# STC12C5A60S2.net
KiCad netlist of a schematic drawn in Altium Designer
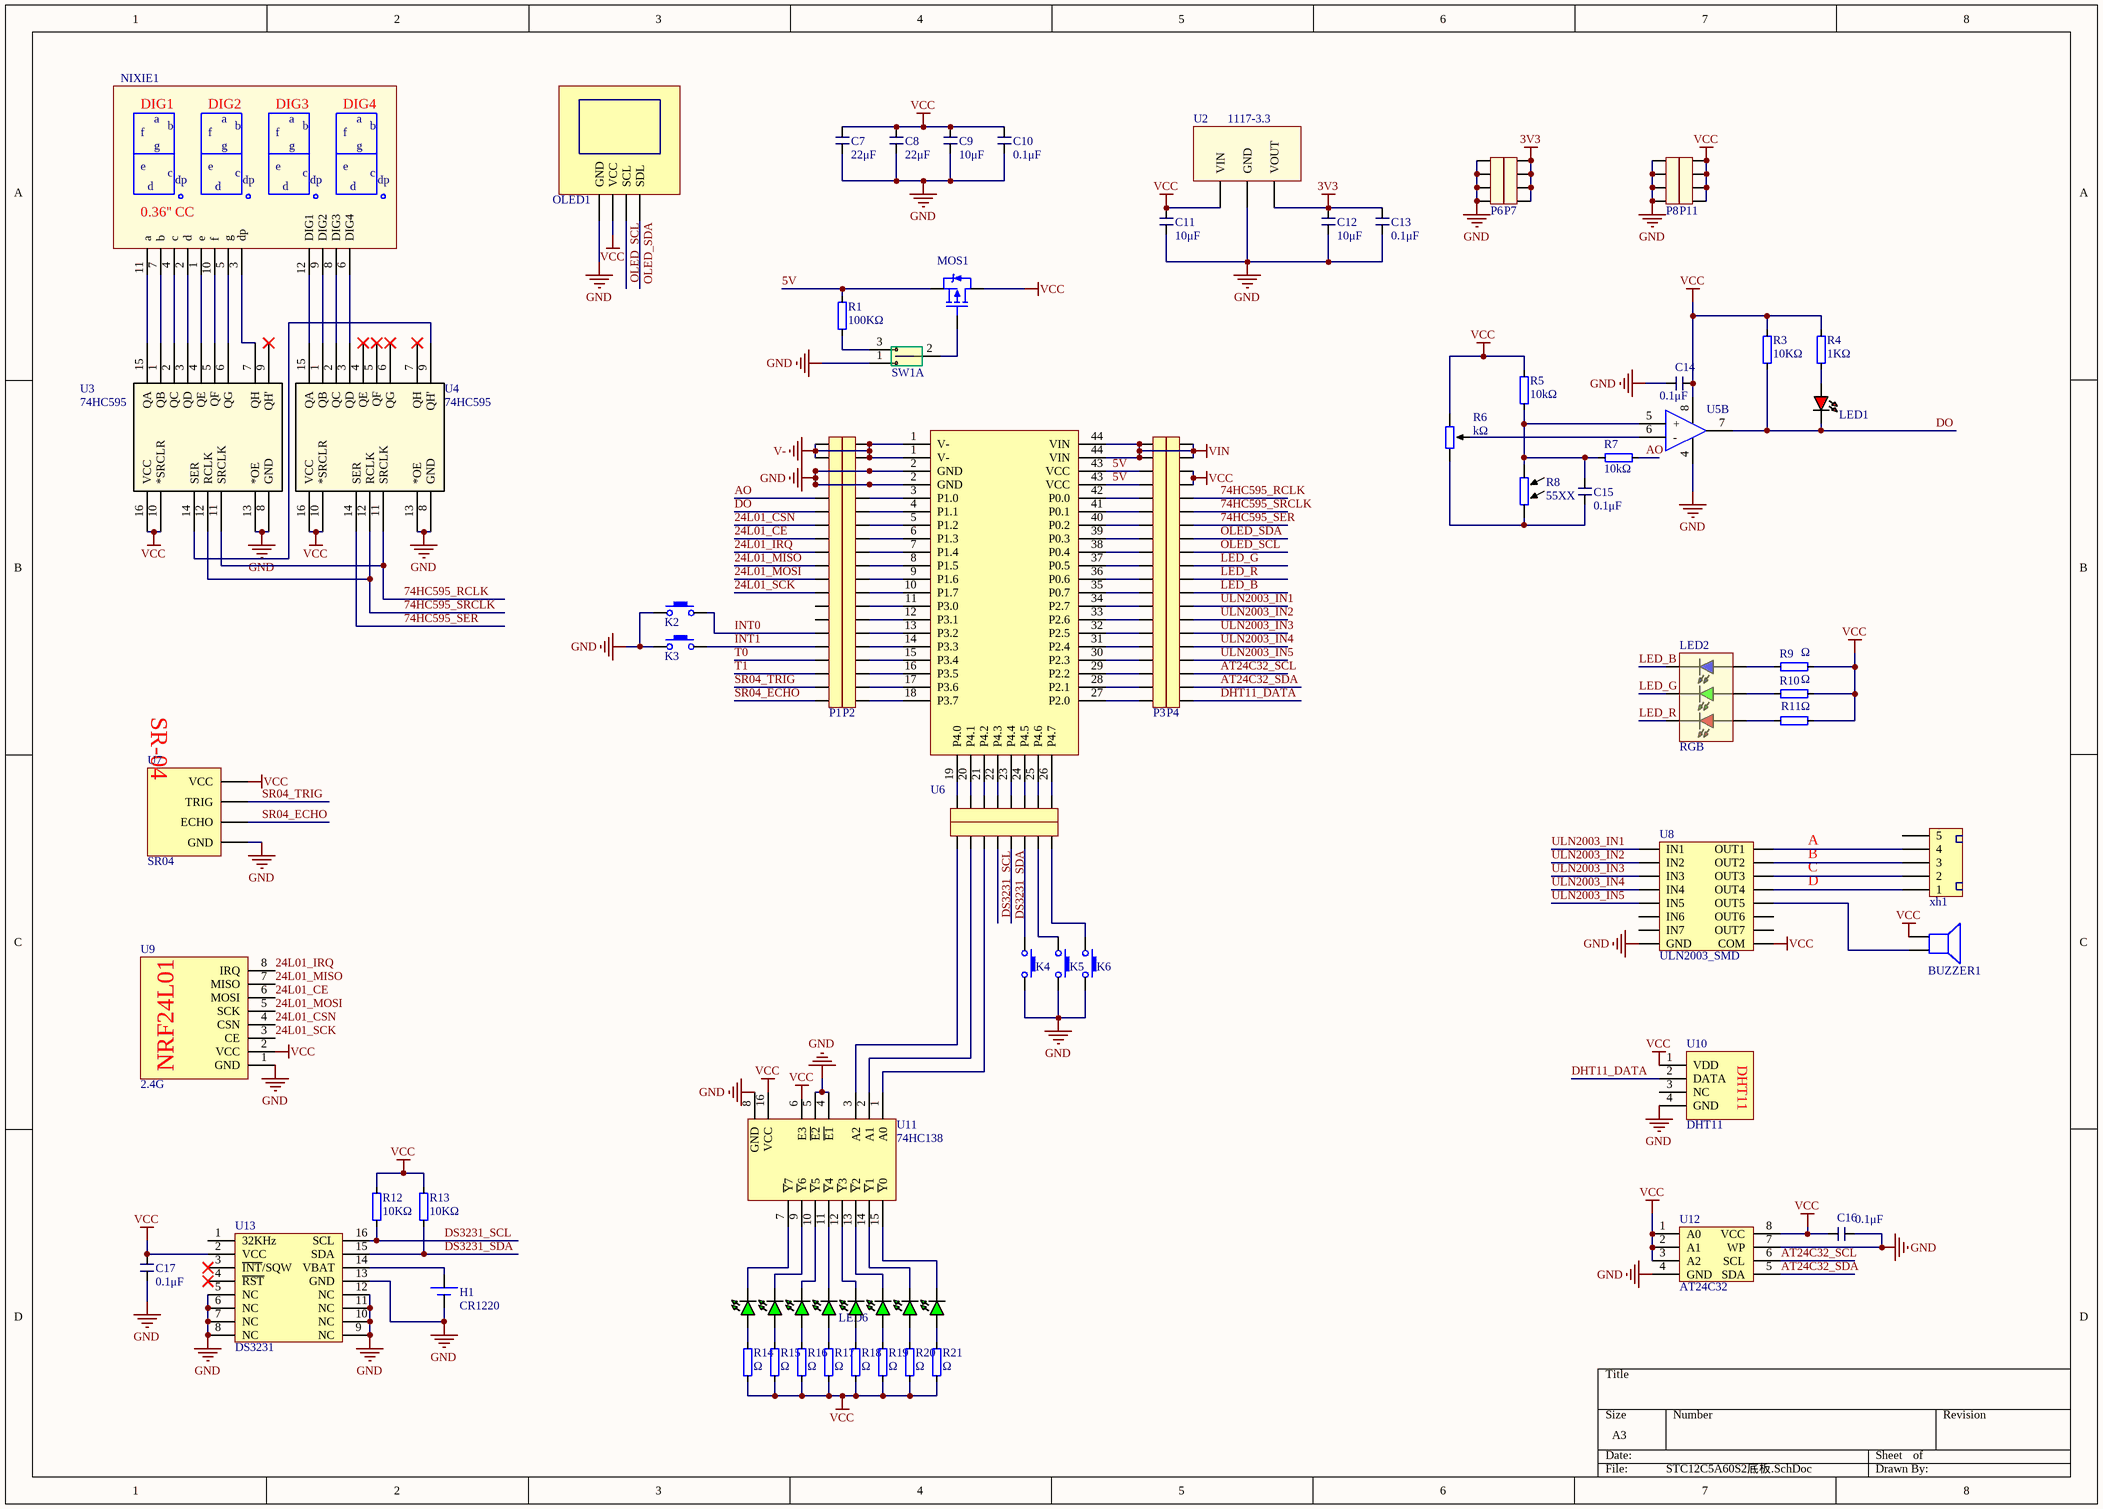
[diagram p0: STC12C5A60S2底板.SchDoc]

(export (version "E")
  (design (tool "Eeschema 10.0.6"))
  (components
    (comp (ref "BUZZER1")
      (value "BUZZER 9.6X5.5_4MM")
      (footprint "BUZZER9.6x4_4mm")
      (libsource (lib "节能库") (part "BUZZER 9.6X5.5_4MM"))
    )
    (comp (ref "C7") (value "22μF") (footprint "C_0805") (libsource (lib "节能库") (part "C_0805")))
    (comp (ref "C8") (value "22μF") (footprint "C_0805") (libsource (lib "节能库") (part "C_0805")))
    (comp (ref "C9") (value "10μF") (footprint "C_0805") (libsource (lib "节能库") (part "C_0805")))
    (comp (ref "C10") (value "0.1μF") (footprint "C_0805") (libsource (lib "节能库") (part "C_0805")))
    (comp (ref "C11") (value "10μF") (footprint "C_0805") (libsource (lib "节能库") (part "C_0805")))
    (comp (ref "C12") (value "10μF") (footprint "C_0805") (libsource (lib "节能库") (part "C_0805")))
    (comp (ref "C13") (value "0.1μF") (footprint "C_0805") (libsource (lib "节能库") (part "C_0805")))
    (comp (ref "C14") (value "0.1μF") (footprint "C_0805") (libsource (lib "节能库") (part "C_0805")))
    (comp (ref "C15") (value "0.1μF") (footprint "C_0805") (libsource (lib "节能库") (part "C_0805")))
    (comp (ref "C16") (value "0.1μF") (footprint "C_0805") (libsource (lib "节能库") (part "C_0805")))
    (comp (ref "C17") (value "0.1μF") (footprint "C_0805") (libsource (lib "节能库") (part "C_0805")))
    (comp (ref "H1")
      (value "CR1220")
      (footprint "holder_CR1220_SMD")
      (libsource (lib "节能库") (part "holder_CR1220_SMD"))
    )
    (comp (ref "K2")
      (value "TACT SWITCH_4_DIP")
      (footprint "TACT SWITCH_4_DIP")
      (libsource (lib "") (part "TACT SWITCH_4_DIP_1"))
    )
    (comp (ref "K3")
      (value "TACT SWITCH_4_DIP")
      (footprint "TACT SWITCH_4_DIP")
      (libsource (lib "") (part "TACT SWITCH_4_DIP_1"))
    )
    (comp (ref "K4")
      (value "TACT SWITCH_4_DIP")
      (footprint "TACT SWITCH_4_DIP")
      (libsource (lib "节能库") (part "TACT SWITCH_4_DIP"))
    )
    (comp (ref "K5")
      (value "TACT SWITCH_4_DIP")
      (footprint "TACT SWITCH_4_DIP")
      (libsource (lib "节能库") (part "TACT SWITCH_4_DIP"))
    )
    (comp (ref "K6")
      (value "TACT SWITCH_4_DIP")
      (footprint "TACT SWITCH_4_DIP")
      (libsource (lib "节能库") (part "TACT SWITCH_4_DIP"))
    )
    (comp (ref "LED1")
      (value "LED_0603-R")
      (footprint "LED_0603-R")
      (libsource (lib "节能库") (part "LED_0603-R"))
    )
    (comp (ref "LED2") (value "RGB") (footprint "LED 5050_RGB") (libsource (lib "节能库") (part "LED_5050_RGB")))
    (comp (ref "LED3")
      (value "LED_0603-G")
      (footprint "LED_0603-G")
      (libsource (lib "节能库") (part "LED_0603-G"))
    )
    (comp (ref "LED4")
      (value "LED_0603-G")
      (footprint "LED_0603-G")
      (libsource (lib "节能库") (part "LED_0603-G"))
    )
    (comp (ref "LED5")
      (value "LED_0603-G")
      (footprint "LED_0603-G")
      (libsource (lib "节能库") (part "LED_0603-G"))
    )
    (comp (ref "LED6")
      (value "LED_0603-G")
      (footprint "LED_0603-G")
      (libsource (lib "节能库") (part "LED_0603-G"))
    )
    (comp (ref "LED7")
      (value "LED_0603-G")
      (footprint "LED_0603-G")
      (libsource (lib "节能库") (part "LED_0603-G"))
    )
    (comp (ref "LED8")
      (value "LED_0603-G")
      (footprint "LED_0603-G")
      (libsource (lib "节能库") (part "LED_0603-G"))
    )
    (comp (ref "LED9")
      (value "LED_0603-G")
      (footprint "LED_0603-G")
      (libsource (lib "节能库") (part "LED_0603-G"))
    )
    (comp (ref "LED10")
      (value "LED_0603-G")
      (footprint "LED_0603-G")
      (libsource (lib "节能库") (part "LED_0603-G"))
    )
    (comp (ref "MOS1") (value "SI2301") (footprint "SOT_23_3") (libsource (lib "节能库") (part "SI2301")))
    (comp (ref "NIXIE1")
      (value "Nixie Tube_CC(0.36in)_4")
      (footprint "Nixie Tube_4(0.36in)")
      (libsource (lib "节能库") (part "Nixie Tube_CC(0.36in)_4"))
    )
    (comp (ref "OLED1")
      (value "0.96''")
      (footprint "OLED 0.96''")
      (libsource (lib "节能库") (part "OLED 0.96''_module"))
    )
    (comp (ref "P1") (value "PIN20") (footprint "PIN_20") (libsource (lib "") (part "PIN20_1")))
    (comp (ref "P2") (value "PIN20") (footprint "PIN_20") (libsource (lib "节能库") (part "PIN20")))
    (comp (ref "P3") (value "PIN20") (footprint "PIN_20") (libsource (lib "") (part "PIN20_1")))
    (comp (ref "P4") (value "PIN20") (footprint "PIN_20") (libsource (lib "节能库") (part "PIN20")))
    (comp (ref "P6") (value "PIN4") (footprint "PIN_4") (libsource (lib "") (part "PIN4_1")))
    (comp (ref "P7") (value "PIN4") (footprint "PIN_4") (libsource (lib "节能库") (part "PIN4")))
    (comp (ref "P8") (value "PIN4") (footprint "PIN_4") (libsource (lib "") (part "PIN4_1")))
    (comp (ref "P11") (value "PIN4") (footprint "PIN_4") (libsource (lib "节能库") (part "PIN4")))
    (comp (ref "P12") (value "PIN8") (footprint "PIN_8") (libsource (lib "") (part "PIN8_1")))
    (comp (ref "P13") (value "PIN8") (footprint "PIN_8") (libsource (lib "节能库") (part "PIN8")))
    (comp (ref "R1") (value "100KΩ") (footprint "R_0805") (libsource (lib "节能库") (part "R_0805")))
    (comp (ref "R3") (value "10KΩ") (footprint "R_0805") (libsource (lib "节能库") (part "R_0805")))
    (comp (ref "R4") (value "1KΩ") (footprint "R_0805") (libsource (lib "节能库") (part "R_0805")))
    (comp (ref "R5") (value "10kΩ") (footprint "R_0805") (libsource (lib "节能库") (part "R_0805")))
    (comp (ref "R6") (value "kΩ") (footprint "RP_3362P") (libsource (lib "节能库") (part "RP_3362P")))
    (comp (ref "R7") (value "10kΩ") (footprint "R_0805") (libsource (lib "节能库") (part "R_0805")))
    (comp (ref "R8") (value "55XX") (footprint "GM55-55XX") (libsource (lib "节能库") (part "GM55-55XX")))
    (comp (ref "R9") (value "Ω") (footprint "R_0805") (libsource (lib "节能库") (part "R_0805")))
    (comp (ref "R10") (value "Ω") (footprint "R_0805") (libsource (lib "节能库") (part "R_0805")))
    (comp (ref "R11") (value "Ω") (footprint "R_0805") (libsource (lib "节能库") (part "R_0805")))
    (comp (ref "R12") (value "10KΩ") (footprint "R_0805") (libsource (lib "节能库") (part "R_0805")))
    (comp (ref "R13") (value "10KΩ") (footprint "R_0805") (libsource (lib "节能库") (part "R_0805")))
    (comp (ref "R14") (value "Ω") (footprint "R_0805") (libsource (lib "节能库") (part "R_0805")))
    (comp (ref "R15") (value "Ω") (footprint "R_0805") (libsource (lib "节能库") (part "R_0805")))
    (comp (ref "R16") (value "Ω") (footprint "R_0805") (libsource (lib "节能库") (part "R_0805")))
    (comp (ref "R17") (value "Ω") (footprint "R_0805") (libsource (lib "节能库") (part "R_0805")))
    (comp (ref "R18") (value "Ω") (footprint "R_0805") (libsource (lib "节能库") (part "R_0805")))
    (comp (ref "R19") (value "Ω") (footprint "R_0805") (libsource (lib "节能库") (part "R_0805")))
    (comp (ref "R20") (value "Ω") (footprint "R_0805") (libsource (lib "节能库") (part "R_0805")))
    (comp (ref "R21") (value "Ω") (footprint "R_0805") (libsource (lib "节能库") (part "R_0805")))
    (comp (ref "SW1")
      (value "switchi_slide(SMD)")
      (footprint "switchi_slide(SMD)")
      (libsource (lib "节能库") (part "switchi_slide(SMD)"))
    )
    (comp (ref "U2") (value "1117-3.3") (footprint "SOT_223") (libsource (lib "节能库") (part "AMS1117-3.3")))
    (comp (ref "U3") (value "74HC595") (footprint "SOP_16") (libsource (lib "节能库") (part "74HC595")))
    (comp (ref "U4") (value "74HC595") (footprint "SOP_16") (libsource (lib "节能库") (part "74HC595")))
    (comp (ref "U5") (value "LM393_DIP") (footprint "SOP_8") (libsource (lib "节能库") (part "LM393_DIP")))
    (comp (ref "U6")
      (value "socket")
      (footprint "STC12_moudle")
      (libsource (lib "节能库") (part "STC12C_module"))
    )
    (comp (ref "U7") (value "SR04") (footprint "SR04") (libsource (lib "节能库") (part "SR04")))
    (comp (ref "U8") (value "ULN2003_SMD") (footprint "SOP_16") (libsource (lib "节能库") (part "ULN2003_SMD")))
    (comp (ref "U9") (value "2.4G") (footprint "NRF24L01") (libsource (lib "节能库") (part "NRF24L01")))
    (comp (ref "U10") (value "DHT11") (footprint "DHT11") (libsource (lib "节能库") (part "DHT11")))
    (comp (ref "U11") (value "74HC138") (footprint "SOP_16") (libsource (lib "节能库") (part "74HC138")))
    (comp (ref "U12") (value "AT24C32") (footprint "SOP_8") (libsource (lib "节能库") (part "AT24C32")))
    (comp (ref "U13") (value "DS3231") (footprint "SOP_16") (libsource (lib "节能库") (part "DS3231_SOP16")))
    (comp (ref "xh1") (value "XH2.54_5") (footprint "XH2.54_5") (libsource (lib "节能库") (part "XH2.54_5")))
  )
  (nets
    (net (code "1") (name "/5V") (class "Default")
      (node (ref "MOS1") (pin "2") (pinfunction "S_2") (pintype "passive"))
      (node (ref "P3") (pin "17") (pinfunction "17_17") (pintype "passive"))
      (node (ref "P3") (pin "18") (pinfunction "18_18") (pintype "passive"))
      (node (ref "R1") (pin "2") (pintype "passive"))
      (node (ref "U6") (pin "43") (pinfunction "VCC_43") (pintype "passive"))
    )
    (net (code "2") (name "/24L01_CE") (class "Default")
      (node (ref "P1") (pin "13") (pinfunction "13_13") (pintype "passive"))
      (node (ref "U9") (pin "6") (pinfunction "MOSI_6") (pintype "passive"))
    )
    (net (code "3") (name "/24L01_CSN") (class "Default")
      (node (ref "P1") (pin "14") (pinfunction "14_14") (pintype "passive"))
      (node (ref "U9") (pin "4") (pinfunction "CSN_4") (pintype "passive"))
    )
    (net (code "4") (name "/24L01_IRQ") (class "Default")
      (node (ref "P1") (pin "12") (pinfunction "12_12") (pintype "passive"))
      (node (ref "U9") (pin "8") (pinfunction "IRQ_8") (pintype "passive"))
    )
    (net (code "5") (name "/24L01_MISO") (class "Default")
      (node (ref "P1") (pin "11") (pinfunction "11_11") (pintype "passive"))
      (node (ref "U9") (pin "7") (pinfunction "MISO_7") (pintype "passive"))
    )
    (net (code "6") (name "/24L01_MOSI") (class "Default")
      (node (ref "P1") (pin "10") (pinfunction "10_10") (pintype "passive"))
      (node (ref "U9") (pin "5") (pinfunction "SCK_5") (pintype "passive"))
    )
    (net (code "7") (name "/24L01_SCK") (class "Default")
      (node (ref "P1") (pin "9") (pinfunction "9_9") (pintype "passive"))
      (node (ref "U9") (pin "3") (pinfunction "CE_3") (pintype "passive"))
    )
    (net (code "8") (name "/74HC595_RCLK") (class "Default")
      (node (ref "P4") (pin "16") (pinfunction "16_16") (pintype "passive"))
      (node (ref "U3") (pin "11") (pinfunction "SRCLK_11") (pintype "passive"))
      (node (ref "U4") (pin "11") (pinfunction "SRCLK_11") (pintype "passive"))
    )
    (net (code "9") (name "/74HC595_SER") (class "Default")
      (node (ref "P4") (pin "14") (pinfunction "14_14") (pintype "passive"))
      (node (ref "U4") (pin "14") (pinfunction "SER_14") (pintype "passive"))
    )
    (net (code "10") (name "/74HC595_SRCLK") (class "Default")
      (node (ref "P4") (pin "15") (pinfunction "15_15") (pintype "passive"))
      (node (ref "U3") (pin "12") (pinfunction "RCLK_12") (pintype "passive"))
      (node (ref "U4") (pin "12") (pinfunction "RCLK_12") (pintype "passive"))
    )
    (net (code "11") (name "/AO") (class "Default")
      (node (ref "P1") (pin "16") (pinfunction "16_16") (pintype "passive"))
      (node (ref "R7") (pin "2") (pintype "passive"))
    )
    (net (code "12") (name "/AT24C32_SCL") (class "Default")
      (node (ref "P4") (pin "3") (pinfunction "3_3") (pintype "passive"))
      (node (ref "U12") (pin "6") (pinfunction "SCL_6") (pintype "passive"))
    )
    (net (code "13") (name "/AT24C32_SDA") (class "Default")
      (node (ref "P4") (pin "2") (pinfunction "2_2") (pintype "passive"))
      (node (ref "U12") (pin "5") (pinfunction "SDA_5") (pintype "passive"))
    )
    (net (code "14") (name "/DHT11_DATA") (class "Default")
      (node (ref "P4") (pin "1") (pinfunction "1_1") (pintype "passive"))
      (node (ref "U10") (pin "2") (pinfunction "DATA_2") (pintype "passive"))
    )
    (net (code "15") (name "/DO") (class "Default")
      (node (ref "LED1") (pin "2") (pinfunction "2_2") (pintype "passive"))
      (node (ref "P1") (pin "15") (pinfunction "15_15") (pintype "passive"))
      (node (ref "R3") (pin "1") (pintype "passive"))
      (node (ref "U5") (pin "7") (pintype "passive"))
    )
    (net (code "16") (name "/DS3231_SCL") (class "Default")
      (node (ref "P13") (pin "4") (pinfunction "4_4") (pintype "passive"))
      (node (ref "R12") (pin "1") (pintype "passive"))
      (node (ref "U13") (pin "16") (pinfunction "SCL_16") (pintype "passive"))
    )
    (net (code "17") (name "/DS3231_SDA") (class "Default")
      (node (ref "P13") (pin "5") (pinfunction "5_5") (pintype "passive"))
      (node (ref "R13") (pin "1") (pintype "passive"))
      (node (ref "U13") (pin "15") (pinfunction "SDA_15") (pintype "passive"))
    )
    (net (code "18") (name "/INT0") (class "Default")
      (node (ref "K2") (pin "2") (pinfunction "2_2") (pintype "passive"))
      (node (ref "P1") (pin "6") (pinfunction "6_6") (pintype "passive"))
    )
    (net (code "19") (name "/INT1") (class "Default")
      (node (ref "K3") (pin "2") (pinfunction "2_2") (pintype "passive"))
      (node (ref "P1") (pin "5") (pinfunction "5_5") (pintype "passive"))
    )
    (net (code "20") (name "/LED_B") (class "Default")
      (node (ref "LED2") (pin "1") (pinfunction "1_1") (pintype "passive"))
      (node (ref "P4") (pin "9") (pinfunction "9_9") (pintype "passive"))
    )
    (net (code "21") (name "/LED_G") (class "Default")
      (node (ref "LED2") (pin "5") (pinfunction "5_5") (pintype "passive"))
      (node (ref "P4") (pin "11") (pinfunction "11_11") (pintype "passive"))
    )
    (net (code "22") (name "/LED_R") (class "Default")
      (node (ref "LED2") (pin "3") (pinfunction "3_3") (pintype "passive"))
      (node (ref "P4") (pin "10") (pinfunction "10_10") (pintype "passive"))
    )
    (net (code "23") (name "/OLED_SCL") (class "Default")
      (node (ref "OLED1") (pin "3") (pinfunction "SCL_3") (pintype "passive"))
      (node (ref "P4") (pin "12") (pinfunction "12_12") (pintype "passive"))
    )
    (net (code "24") (name "/OLED_SDA") (class "Default")
      (node (ref "OLED1") (pin "4") (pinfunction "SDL_4") (pintype "passive"))
      (node (ref "P4") (pin "13") (pinfunction "13_13") (pintype "passive"))
    )
    (net (code "25") (name "/SR04_ECHO") (class "Default")
      (node (ref "P1") (pin "1") (pinfunction "1_1") (pintype "passive"))
      (node (ref "U7") (pin "3") (pinfunction "ECHO_3") (pintype "passive"))
    )
    (net (code "26") (name "/SR04_TRIG") (class "Default")
      (node (ref "P1") (pin "2") (pinfunction "2_2") (pintype "passive"))
      (node (ref "U7") (pin "2") (pinfunction "TRIG_2") (pintype "passive"))
    )
    (net (code "27") (name "/T0") (class "Default")
      (node (ref "P1") (pin "4") (pinfunction "4_4") (pintype "passive"))
    )
    (net (code "28") (name "/T1") (class "Default")
      (node (ref "P1") (pin "3") (pinfunction "3_3") (pintype "passive"))
    )
    (net (code "29") (name "/ULN2003_IN1") (class "Default")
      (node (ref "P4") (pin "8") (pinfunction "8_8") (pintype "passive"))
      (node (ref "U8") (pin "1") (pinfunction "IN1_1") (pintype "passive"))
    )
    (net (code "30") (name "/ULN2003_IN2") (class "Default")
      (node (ref "P4") (pin "7") (pinfunction "7_7") (pintype "passive"))
      (node (ref "U8") (pin "2") (pinfunction "IN2_2") (pintype "passive"))
    )
    (net (code "31") (name "/ULN2003_IN3") (class "Default")
      (node (ref "P4") (pin "6") (pinfunction "6_6") (pintype "passive"))
      (node (ref "U8") (pin "3") (pinfunction "IN3_3") (pintype "passive"))
    )
    (net (code "32") (name "/ULN2003_IN4") (class "Default")
      (node (ref "P4") (pin "5") (pinfunction "5_5") (pintype "passive"))
      (node (ref "U8") (pin "4") (pinfunction "IN4_4") (pintype "passive"))
    )
    (net (code "33") (name "/ULN2003_IN5") (class "Default")
      (node (ref "P4") (pin "4") (pinfunction "4_4") (pintype "passive"))
      (node (ref "U8") (pin "5") (pinfunction "IN5_5") (pintype "passive"))
    )
    (net (code "34") (name "3V3") (class "Default")
      (node (ref "C12") (pin "1") (pinfunction "1_1") (pintype "passive"))
      (node (ref "C13") (pin "1") (pinfunction "1_1") (pintype "passive"))
      (node (ref "P7") (pin "1") (pinfunction "1_1") (pintype "passive"))
      (node (ref "P7") (pin "2") (pinfunction "2_2") (pintype "passive"))
      (node (ref "P7") (pin "3") (pinfunction "3_3") (pintype "passive"))
      (node (ref "P7") (pin "4") (pinfunction "4_4") (pintype "passive"))
      (node (ref "U2") (pin "2") (pinfunction "VOUT_2") (pintype "passive"))
    )
    (net (code "35") (name "GND") (class "Default")
      (node (ref "C10") (pin "2") (pinfunction "2_2") (pintype "passive"))
      (node (ref "C11") (pin "2") (pinfunction "2_2") (pintype "passive"))
      (node (ref "C12") (pin "2") (pinfunction "2_2") (pintype "passive"))
      (node (ref "C13") (pin "2") (pinfunction "2_2") (pintype "passive"))
      (node (ref "C14") (pin "1") (pinfunction "1_1") (pintype "passive"))
      (node (ref "C16") (pin "2") (pinfunction "2_2") (pintype "passive"))
      (node (ref "C17") (pin "2") (pinfunction "2_2") (pintype "passive"))
      (node (ref "C7") (pin "2") (pinfunction "2_2") (pintype "passive"))
      (node (ref "C8") (pin "2") (pinfunction "2_2") (pintype "passive"))
      (node (ref "C9") (pin "2") (pinfunction "2_2") (pintype "passive"))
      (node (ref "H1") (pin "2") (pinfunction "-_2") (pintype "passive"))
      (node (ref "K2") (pin "1") (pinfunction "1_1") (pintype "passive"))
      (node (ref "K3") (pin "1") (pinfunction "1_1") (pintype "passive"))
      (node (ref "K4") (pin "2") (pinfunction "2_2") (pintype "passive"))
      (node (ref "K5") (pin "2") (pinfunction "2_2") (pintype "passive"))
      (node (ref "K6") (pin "2") (pinfunction "2_2") (pintype "passive"))
      (node (ref "OLED1") (pin "1") (pinfunction "GND_1") (pintype "passive"))
      (node (ref "P1") (pin "17") (pinfunction "17_17") (pintype "passive"))
      (node (ref "P1") (pin "18") (pinfunction "18_18") (pintype "passive"))
      (node (ref "P2") (pin "17") (pinfunction "17_17") (pintype "passive"))
      (node (ref "P2") (pin "18") (pinfunction "18_18") (pintype "passive"))
      (node (ref "P6") (pin "1") (pinfunction "1_1") (pintype "passive"))
      (node (ref "P6") (pin "2") (pinfunction "2_2") (pintype "passive"))
      (node (ref "P6") (pin "3") (pinfunction "3_3") (pintype "passive"))
      (node (ref "P6") (pin "4") (pinfunction "4_4") (pintype "passive"))
      (node (ref "P8") (pin "1") (pinfunction "1_1") (pintype "passive"))
      (node (ref "P8") (pin "2") (pinfunction "2_2") (pintype "passive"))
      (node (ref "P8") (pin "3") (pinfunction "3_3") (pintype "passive"))
      (node (ref "P8") (pin "4") (pinfunction "4_4") (pintype "passive"))
      (node (ref "SW1") (pin "1") (pinfunction "1_1") (pintype "passive"))
      (node (ref "U10") (pin "4") (pinfunction "GND_4") (pintype "passive"))
      (node (ref "U11") (pin "4") (pinfunction "~{E1}_4") (pintype "passive"))
      (node (ref "U11") (pin "5") (pinfunction "~{E2}_5") (pintype "passive"))
      (node (ref "U11") (pin "8") (pinfunction "GND_8") (pintype "passive"))
      (node (ref "U12") (pin "4") (pinfunction "GND_4") (pintype "passive"))
      (node (ref "U12") (pin "7") (pinfunction "WP_7") (pintype "passive"))
      (node (ref "U13") (pin "10") (pinfunction "NC_10") (pintype "passive"))
      (node (ref "U13") (pin "11") (pinfunction "NC_11") (pintype "passive"))
      (node (ref "U13") (pin "12") (pinfunction "NC_12") (pintype "passive"))
      (node (ref "U13") (pin "13") (pinfunction "GND_13") (pintype "passive"))
      (node (ref "U13") (pin "5") (pinfunction "NC_5") (pintype "passive"))
      (node (ref "U13") (pin "6") (pinfunction "NC_6") (pintype "passive"))
      (node (ref "U13") (pin "7") (pinfunction "NC_7") (pintype "passive"))
      (node (ref "U13") (pin "8") (pinfunction "NC_8") (pintype "passive"))
      (node (ref "U13") (pin "9") (pinfunction "NC_9") (pintype "passive"))
      (node (ref "U2") (pin "1") (pinfunction "GND_1") (pintype "passive"))
      (node (ref "U3") (pin "13") (pinfunction "*OE_13") (pintype "passive"))
      (node (ref "U3") (pin "8") (pinfunction "GND_8") (pintype "passive"))
      (node (ref "U4") (pin "13") (pinfunction "*OE_13") (pintype "passive"))
      (node (ref "U4") (pin "8") (pinfunction "GND_8") (pintype "passive"))
      (node (ref "U5") (pin "4") (pinfunction "GND_4") (pintype "passive"))
      (node (ref "U6") (pin "2") (pinfunction "GND_2") (pintype "passive"))
      (node (ref "U7") (pin "4") (pinfunction "GND_4") (pintype "passive"))
      (node (ref "U8") (pin "8") (pinfunction "GND_8") (pintype "passive"))
      (node (ref "U9") (pin "1") (pinfunction "GND_1") (pintype "passive"))
    )
    (net (code "36") (name "Net-(C15-Pad2)") (class "Default")
      (node (ref "C15") (pin "2") (pinfunction "2_2") (pintype "passive"))
      (node (ref "R6") (pin "3") (pinfunction "3_3") (pintype "passive"))
      (node (ref "R8") (pin "2") (pintype "passive"))
    )
    (net (code "37") (name "Net-(H1-+)") (class "Default")
      (node (ref "H1") (pin "1") (pinfunction "+_1") (pintype "passive"))
      (node (ref "U13") (pin "14") (pinfunction "VBAT_14") (pintype "passive"))
    )
    (net (code "38") (name "Net-(K4-Pad1)") (class "Default")
      (node (ref "K4") (pin "1") (pinfunction "1_1") (pintype "passive"))
      (node (ref "P13") (pin "6") (pinfunction "6_6") (pintype "passive"))
    )
    (net (code "39") (name "Net-(K5-Pad1)") (class "Default")
      (node (ref "K5") (pin "1") (pinfunction "1_1") (pintype "passive"))
      (node (ref "P13") (pin "7") (pinfunction "7_7") (pintype "passive"))
    )
    (net (code "40") (name "Net-(K6-Pad1)") (class "Default")
      (node (ref "K6") (pin "1") (pinfunction "1_1") (pintype "passive"))
      (node (ref "P13") (pin "8") (pinfunction "8_8") (pintype "passive"))
    )
    (net (code "41") (name "Net-(LED1-Pad1)") (class "Default")
      (node (ref "LED1") (pin "1") (pinfunction "1_1") (pintype "passive"))
      (node (ref "R4") (pin "1") (pintype "passive"))
    )
    (net (code "42") (name "Net-(LED2-Pad2)") (class "Default")
      (node (ref "LED2") (pin "2") (pinfunction "2_2") (pintype "passive"))
      (node (ref "R9") (pin "1") (pintype "passive"))
    )
    (net (code "43") (name "Net-(LED2-Pad4)") (class "Default")
      (node (ref "LED2") (pin "4") (pinfunction "4_4") (pintype "passive"))
      (node (ref "R11") (pin "1") (pintype "passive"))
    )
    (net (code "44") (name "Net-(LED2-Pad6)") (class "Default")
      (node (ref "LED2") (pin "6") (pinfunction "6_6") (pintype "passive"))
      (node (ref "R10") (pin "1") (pintype "passive"))
    )
    (net (code "45") (name "Net-(LED3-Pad1)") (class "Default")
      (node (ref "LED3") (pin "1") (pinfunction "1_1") (pintype "passive"))
      (node (ref "R14") (pin "2") (pintype "passive"))
    )
    (net (code "46") (name "Net-(LED4-Pad1)") (class "Default")
      (node (ref "LED4") (pin "1") (pinfunction "1_1") (pintype "passive"))
      (node (ref "R15") (pin "2") (pintype "passive"))
    )
    (net (code "47") (name "Net-(LED5-Pad1)") (class "Default")
      (node (ref "LED5") (pin "1") (pinfunction "1_1") (pintype "passive"))
      (node (ref "R16") (pin "2") (pintype "passive"))
    )
    (net (code "48") (name "Net-(LED6-Pad1)") (class "Default")
      (node (ref "LED6") (pin "1") (pinfunction "1_1") (pintype "passive"))
      (node (ref "R17") (pin "2") (pintype "passive"))
    )
    (net (code "49") (name "Net-(LED7-Pad1)") (class "Default")
      (node (ref "LED7") (pin "1") (pinfunction "1_1") (pintype "passive"))
      (node (ref "R18") (pin "2") (pintype "passive"))
    )
    (net (code "50") (name "Net-(LED8-Pad1)") (class "Default")
      (node (ref "LED8") (pin "1") (pinfunction "1_1") (pintype "passive"))
      (node (ref "R19") (pin "2") (pintype "passive"))
    )
    (net (code "51") (name "Net-(LED9-Pad1)") (class "Default")
      (node (ref "LED9") (pin "1") (pinfunction "1_1") (pintype "passive"))
      (node (ref "R20") (pin "2") (pintype "passive"))
    )
    (net (code "52") (name "Net-(LED10-Pad1)") (class "Default")
      (node (ref "LED10") (pin "1") (pinfunction "1_1") (pintype "passive"))
      (node (ref "R21") (pin "2") (pintype "passive"))
    )
    (net (code "53") (name "Net-(MOS1-G)") (class "Default")
      (node (ref "MOS1") (pin "1") (pinfunction "G_1") (pintype "passive"))
      (node (ref "SW1") (pin "2") (pinfunction "2_2") (pintype "passive"))
    )
    (net (code "54") (name "Net-(NIXIE1-DIG1)") (class "Default")
      (node (ref "NIXIE1") (pin "12") (pinfunction "DIG1_12") (pintype "passive"))
      (node (ref "U4") (pin "15") (pinfunction "QA_15") (pintype "passive"))
    )
    (net (code "55") (name "Net-(NIXIE1-DIG2)") (class "Default")
      (node (ref "NIXIE1") (pin "9") (pinfunction "DIG2_9") (pintype "passive"))
      (node (ref "U4") (pin "1") (pinfunction "QB_1") (pintype "passive"))
    )
    (net (code "56") (name "Net-(NIXIE1-DIG3)") (class "Default")
      (node (ref "NIXIE1") (pin "8") (pinfunction "DIG3_8") (pintype "passive"))
      (node (ref "U4") (pin "2") (pinfunction "QC_2") (pintype "passive"))
    )
    (net (code "57") (name "Net-(NIXIE1-DIG4)") (class "Default")
      (node (ref "NIXIE1") (pin "6") (pinfunction "DIG4_6") (pintype "passive"))
      (node (ref "U4") (pin "3") (pinfunction "QD_3") (pintype "passive"))
    )
    (net (code "58") (name "Net-(NIXIE1-a)") (class "Default")
      (node (ref "NIXIE1") (pin "11") (pinfunction "a_11") (pintype "passive"))
      (node (ref "U3") (pin "15") (pinfunction "QA_15") (pintype "passive"))
    )
    (net (code "59") (name "Net-(NIXIE1-b)") (class "Default")
      (node (ref "NIXIE1") (pin "7") (pinfunction "b_7") (pintype "passive"))
      (node (ref "U3") (pin "1") (pinfunction "QB_1") (pintype "passive"))
    )
    (net (code "60") (name "Net-(NIXIE1-c)") (class "Default")
      (node (ref "NIXIE1") (pin "4") (pinfunction "c_4") (pintype "passive"))
      (node (ref "U3") (pin "2") (pinfunction "QC_2") (pintype "passive"))
    )
    (net (code "61") (name "Net-(NIXIE1-d)") (class "Default")
      (node (ref "NIXIE1") (pin "2") (pinfunction "d_2") (pintype "passive"))
      (node (ref "U3") (pin "3") (pinfunction "QD_3") (pintype "passive"))
    )
    (net (code "62") (name "Net-(NIXIE1-dp)") (class "Default")
      (node (ref "NIXIE1") (pin "3") (pinfunction "dp_3") (pintype "passive"))
      (node (ref "U3") (pin "7") (pinfunction "QH_7") (pintype "passive"))
    )
    (net (code "63") (name "Net-(NIXIE1-e)") (class "Default")
      (node (ref "NIXIE1") (pin "1") (pinfunction "e_1") (pintype "passive"))
      (node (ref "U3") (pin "4") (pinfunction "QE_4") (pintype "passive"))
    )
    (net (code "64") (name "Net-(NIXIE1-f)") (class "Default")
      (node (ref "NIXIE1") (pin "10") (pinfunction "f_10") (pintype "passive"))
      (node (ref "U3") (pin "5") (pinfunction "QF_5") (pintype "passive"))
    )
    (net (code "65") (name "Net-(NIXIE1-g)") (class "Default")
      (node (ref "NIXIE1") (pin "5") (pinfunction "g_5") (pintype "passive"))
      (node (ref "U3") (pin "6") (pinfunction "QG_6") (pintype "passive"))
    )
    (net (code "66") (name "Net-(R1-Pad1)") (class "Default")
      (node (ref "R1") (pin "1") (pintype "passive"))
      (node (ref "SW1") (pin "3") (pinfunction "3_3") (pintype "passive"))
    )
    (net (code "67") (name "Net-(U3-SER)") (class "Default")
      (node (ref "U3") (pin "14") (pinfunction "SER_14") (pintype "passive"))
      (node (ref "U4") (pin "9") (pinfunction "QH'_9") (pintype "passive"))
    )
    (net (code "68") (name "Net-(U5B-+)") (class "Default")
      (node (ref "C15") (pin "1") (pinfunction "1_1") (pintype "passive"))
      (node (ref "R5") (pin "2") (pintype "passive"))
      (node (ref "R7") (pin "1") (pintype "passive"))
      (node (ref "R8") (pin "1") (pintype "passive"))
      (node (ref "U5") (pin "5") (pinfunction "+_5") (pintype "passive"))
    )
    (net (code "69") (name "Net-(U5B--)") (class "Default")
      (node (ref "R6") (pin "2") (pinfunction "2_2") (pintype "passive"))
      (node (ref "U5") (pin "6") (pinfunction "-_6") (pintype "passive"))
    )
    (net (code "70") (name "Net-(U6-P0.0)") (class "Default")
      (node (ref "P3") (pin "16") (pinfunction "16_16") (pintype "passive"))
      (node (ref "U6") (pin "42") (pinfunction "P0.0_42") (pintype "passive"))
    )
    (net (code "71") (name "Net-(U6-P0.1)") (class "Default")
      (node (ref "P3") (pin "15") (pinfunction "15_15") (pintype "passive"))
      (node (ref "U6") (pin "41") (pinfunction "P0.1_41") (pintype "passive"))
    )
    (net (code "72") (name "Net-(U6-P0.2)") (class "Default")
      (node (ref "P3") (pin "14") (pinfunction "14_14") (pintype "passive"))
      (node (ref "U6") (pin "40") (pinfunction "P0.2_40") (pintype "passive"))
    )
    (net (code "73") (name "Net-(U6-P0.3)") (class "Default")
      (node (ref "P3") (pin "13") (pinfunction "13_13") (pintype "passive"))
      (node (ref "U6") (pin "39") (pinfunction "P0.3_39") (pintype "passive"))
    )
    (net (code "74") (name "Net-(U6-P0.4)") (class "Default")
      (node (ref "P3") (pin "12") (pinfunction "12_12") (pintype "passive"))
      (node (ref "U6") (pin "38") (pinfunction "P0.4_38") (pintype "passive"))
    )
    (net (code "75") (name "Net-(U6-P0.5)") (class "Default")
      (node (ref "P3") (pin "11") (pinfunction "11_11") (pintype "passive"))
      (node (ref "U6") (pin "37") (pinfunction "P0.5_37") (pintype "passive"))
    )
    (net (code "76") (name "Net-(U6-P0.6)") (class "Default")
      (node (ref "P3") (pin "10") (pinfunction "10_10") (pintype "passive"))
      (node (ref "U6") (pin "36") (pinfunction "P0.6_36") (pintype "passive"))
    )
    (net (code "77") (name "Net-(U6-P0.7)") (class "Default")
      (node (ref "P3") (pin "9") (pinfunction "9_9") (pintype "passive"))
      (node (ref "U6") (pin "35") (pinfunction "P0.7_35") (pintype "passive"))
    )
    (net (code "78") (name "Net-(U6-P1.0)") (class "Default")
      (node (ref "P2") (pin "16") (pinfunction "16_16") (pintype "passive"))
      (node (ref "U6") (pin "3") (pinfunction "P1.0_3") (pintype "passive"))
    )
    (net (code "79") (name "Net-(U6-P1.1)") (class "Default")
      (node (ref "P2") (pin "15") (pinfunction "15_15") (pintype "passive"))
      (node (ref "U6") (pin "4") (pinfunction "P1.1_4") (pintype "passive"))
    )
    (net (code "80") (name "Net-(U6-P1.2)") (class "Default")
      (node (ref "P2") (pin "14") (pinfunction "14_14") (pintype "passive"))
      (node (ref "U6") (pin "5") (pinfunction "P1.2_5") (pintype "passive"))
    )
    (net (code "81") (name "Net-(U6-P1.3)") (class "Default")
      (node (ref "P2") (pin "13") (pinfunction "13_13") (pintype "passive"))
      (node (ref "U6") (pin "6") (pinfunction "P1.3_6") (pintype "passive"))
    )
    (net (code "82") (name "Net-(U6-P1.4)") (class "Default")
      (node (ref "P2") (pin "12") (pinfunction "12_12") (pintype "passive"))
      (node (ref "U6") (pin "7") (pinfunction "P1.4_7") (pintype "passive"))
    )
    (net (code "83") (name "Net-(U6-P1.5)") (class "Default")
      (node (ref "P2") (pin "11") (pinfunction "11_11") (pintype "passive"))
      (node (ref "U6") (pin "8") (pinfunction "P1.5_8") (pintype "passive"))
    )
    (net (code "84") (name "Net-(U6-P1.6)") (class "Default")
      (node (ref "P2") (pin "10") (pinfunction "10_10") (pintype "passive"))
      (node (ref "U6") (pin "9") (pinfunction "P1.6_9") (pintype "passive"))
    )
    (net (code "85") (name "Net-(U6-P1.7)") (class "Default")
      (node (ref "P2") (pin "9") (pinfunction "9_9") (pintype "passive"))
      (node (ref "U6") (pin "10") (pinfunction "P1.7_10") (pintype "passive"))
    )
    (net (code "86") (name "Net-(U6-P2.0)") (class "Default")
      (node (ref "P3") (pin "1") (pinfunction "1_1") (pintype "passive"))
      (node (ref "U6") (pin "27") (pinfunction "P2.0_27") (pintype "passive"))
    )
    (net (code "87") (name "Net-(U6-P2.1)") (class "Default")
      (node (ref "P3") (pin "2") (pinfunction "2_2") (pintype "passive"))
      (node (ref "U6") (pin "28") (pinfunction "P2.1_28") (pintype "passive"))
    )
    (net (code "88") (name "Net-(U6-P2.2)") (class "Default")
      (node (ref "P3") (pin "3") (pinfunction "3_3") (pintype "passive"))
      (node (ref "U6") (pin "29") (pinfunction "P2.2_29") (pintype "passive"))
    )
    (net (code "89") (name "Net-(U6-P2.3)") (class "Default")
      (node (ref "P3") (pin "4") (pinfunction "4_4") (pintype "passive"))
      (node (ref "U6") (pin "30") (pinfunction "P2.3_30") (pintype "passive"))
    )
    (net (code "90") (name "Net-(U6-P2.4)") (class "Default")
      (node (ref "P3") (pin "5") (pinfunction "5_5") (pintype "passive"))
      (node (ref "U6") (pin "31") (pinfunction "P2.4_31") (pintype "passive"))
    )
    (net (code "91") (name "Net-(U6-P2.5)") (class "Default")
      (node (ref "P3") (pin "6") (pinfunction "6_6") (pintype "passive"))
      (node (ref "U6") (pin "32") (pinfunction "P2.5_32") (pintype "passive"))
    )
    (net (code "92") (name "Net-(U6-P2.6)") (class "Default")
      (node (ref "P3") (pin "7") (pinfunction "7_7") (pintype "passive"))
      (node (ref "U6") (pin "33") (pinfunction "P2.6_33") (pintype "passive"))
    )
    (net (code "93") (name "Net-(U6-P2.7)") (class "Default")
      (node (ref "P3") (pin "8") (pinfunction "8_8") (pintype "passive"))
      (node (ref "U6") (pin "34") (pinfunction "P2.7_34") (pintype "passive"))
    )
    (net (code "94") (name "Net-(U6-P3.0)") (class "Default")
      (node (ref "P2") (pin "8") (pinfunction "8_8") (pintype "passive"))
      (node (ref "U6") (pin "11") (pinfunction "P3.0_11") (pintype "passive"))
    )
    (net (code "95") (name "Net-(U6-P3.1)") (class "Default")
      (node (ref "P2") (pin "7") (pinfunction "7_7") (pintype "passive"))
      (node (ref "U6") (pin "12") (pinfunction "P3.1_12") (pintype "passive"))
    )
    (net (code "96") (name "Net-(U6-P3.2)") (class "Default")
      (node (ref "P2") (pin "6") (pinfunction "6_6") (pintype "passive"))
      (node (ref "U6") (pin "13") (pinfunction "P3.2_13") (pintype "passive"))
    )
    (net (code "97") (name "Net-(U6-P3.3)") (class "Default")
      (node (ref "P2") (pin "5") (pinfunction "5_5") (pintype "passive"))
      (node (ref "U6") (pin "14") (pinfunction "P3.3_14") (pintype "passive"))
    )
    (net (code "98") (name "Net-(U6-P3.4)") (class "Default")
      (node (ref "P2") (pin "4") (pinfunction "4_4") (pintype "passive"))
      (node (ref "U6") (pin "15") (pinfunction "P3.4_15") (pintype "passive"))
    )
    (net (code "99") (name "Net-(U6-P3.5)") (class "Default")
      (node (ref "P2") (pin "3") (pinfunction "3_3") (pintype "passive"))
      (node (ref "U6") (pin "16") (pinfunction "P3.5_16") (pintype "passive"))
    )
    (net (code "100") (name "Net-(U6-P3.6)") (class "Default")
      (node (ref "P2") (pin "2") (pinfunction "2_2") (pintype "passive"))
      (node (ref "U6") (pin "17") (pinfunction "P3.6_17") (pintype "passive"))
    )
    (net (code "101") (name "Net-(U6-P3.7)") (class "Default")
      (node (ref "P2") (pin "1") (pinfunction "1_1") (pintype "passive"))
      (node (ref "U6") (pin "18") (pinfunction "P3.7_18") (pintype "passive"))
    )
    (net (code "102") (name "Net-(U6-P4.0)") (class "Default")
      (node (ref "P12") (pin "1") (pinfunction "1_1") (pintype "passive"))
      (node (ref "U6") (pin "19") (pinfunction "P4.0_19") (pintype "passive"))
    )
    (net (code "103") (name "Net-(U6-P4.1)") (class "Default")
      (node (ref "P12") (pin "2") (pinfunction "2_2") (pintype "passive"))
      (node (ref "U6") (pin "20") (pinfunction "P4.1_20") (pintype "passive"))
    )
    (net (code "104") (name "Net-(U6-P4.2)") (class "Default")
      (node (ref "P12") (pin "3") (pinfunction "3_3") (pintype "passive"))
      (node (ref "U6") (pin "21") (pinfunction "P4.2_21") (pintype "passive"))
    )
    (net (code "105") (name "Net-(U6-P4.3)") (class "Default")
      (node (ref "P12") (pin "4") (pinfunction "4_4") (pintype "passive"))
      (node (ref "U6") (pin "22") (pinfunction "P4.3_22") (pintype "passive"))
    )
    (net (code "106") (name "Net-(U6-P4.4)") (class "Default")
      (node (ref "P12") (pin "5") (pinfunction "5_5") (pintype "passive"))
      (node (ref "U6") (pin "23") (pinfunction "P4.4_23") (pintype "passive"))
    )
    (net (code "107") (name "Net-(U6-P4.5)") (class "Default")
      (node (ref "P12") (pin "6") (pinfunction "6_6") (pintype "passive"))
      (node (ref "U6") (pin "24") (pinfunction "P4.5_24") (pintype "passive"))
    )
    (net (code "108") (name "Net-(U6-P4.6)") (class "Default")
      (node (ref "P12") (pin "7") (pinfunction "7_7") (pintype "passive"))
      (node (ref "U6") (pin "25") (pinfunction "P4.6_25") (pintype "passive"))
    )
    (net (code "109") (name "Net-(U6-P4.7)") (class "Default")
      (node (ref "P12") (pin "8") (pinfunction "8_8") (pintype "passive"))
      (node (ref "U6") (pin "26") (pinfunction "P4.7_26") (pintype "passive"))
    )
    (net (code "110") (name "Net-(U8-OUT1)") (class "Default")
      (node (ref "U8") (pin "16") (pinfunction "OUT1_16") (pintype "passive"))
      (node (ref "xh1") (pin "4") (pinfunction "4_4") (pintype "passive"))
    )
    (net (code "111") (name "Net-(U8-OUT2)") (class "Default")
      (node (ref "U8") (pin "15") (pinfunction "OUT2_15") (pintype "passive"))
      (node (ref "xh1") (pin "3") (pinfunction "3_3") (pintype "passive"))
    )
    (net (code "112") (name "Net-(U8-OUT3)") (class "Default")
      (node (ref "U8") (pin "14") (pinfunction "OUT3_14") (pintype "passive"))
      (node (ref "xh1") (pin "2") (pinfunction "2_2") (pintype "passive"))
    )
    (net (code "113") (name "Net-(U8-OUT4)") (class "Default")
      (node (ref "U8") (pin "13") (pinfunction "OUT4_13") (pintype "passive"))
      (node (ref "xh1") (pin "1") (pinfunction "1_1") (pintype "passive"))
    )
    (net (code "114") (name "Net-(U8-OUT5)") (class "Default")
      (node (ref "BUZZER1") (pin "2") (pinfunction "2_2") (pintype "passive"))
      (node (ref "U8") (pin "12") (pinfunction "OUT5_12") (pintype "passive"))
    )
    (net (code "115") (name "Net-(U11-A0)") (class "Default")
      (node (ref "P13") (pin "3") (pinfunction "3_3") (pintype "passive"))
      (node (ref "U11") (pin "1") (pinfunction "A0_1") (pintype "passive"))
    )
    (net (code "116") (name "Net-(U11-A1)") (class "Default")
      (node (ref "P13") (pin "2") (pinfunction "2_2") (pintype "passive"))
      (node (ref "U11") (pin "2") (pinfunction "A1_2") (pintype "passive"))
    )
    (net (code "117") (name "Net-(U11-A2)") (class "Default")
      (node (ref "P13") (pin "1") (pinfunction "1_1") (pintype "passive"))
      (node (ref "U11") (pin "3") (pinfunction "A2_3") (pintype "passive"))
    )
    (net (code "118") (name "Net-(U11-~{Y}0)") (class "Default")
      (node (ref "LED10") (pin "2") (pinfunction "2_2") (pintype "passive"))
      (node (ref "U11") (pin "15") (pinfunction "~{Y}0_15") (pintype "passive"))
    )
    (net (code "119") (name "Net-(U11-~{Y}1)") (class "Default")
      (node (ref "LED9") (pin "2") (pinfunction "2_2") (pintype "passive"))
      (node (ref "U11") (pin "14") (pinfunction "~{Y}1_14") (pintype "passive"))
    )
    (net (code "120") (name "Net-(U11-~{Y}2)") (class "Default")
      (node (ref "LED8") (pin "2") (pinfunction "2_2") (pintype "passive"))
      (node (ref "U11") (pin "13") (pinfunction "~{Y}2_13") (pintype "passive"))
    )
    (net (code "121") (name "Net-(U11-~{Y}3)") (class "Default")
      (node (ref "LED7") (pin "2") (pinfunction "2_2") (pintype "passive"))
      (node (ref "U11") (pin "12") (pinfunction "~{Y}3_12") (pintype "passive"))
    )
    (net (code "122") (name "Net-(U11-~{Y}4)") (class "Default")
      (node (ref "LED6") (pin "2") (pinfunction "2_2") (pintype "passive"))
      (node (ref "U11") (pin "11") (pinfunction "~{Y}4_11") (pintype "passive"))
    )
    (net (code "123") (name "Net-(U11-~{Y}5)") (class "Default")
      (node (ref "LED5") (pin "2") (pinfunction "2_2") (pintype "passive"))
      (node (ref "U11") (pin "10") (pinfunction "~{Y}5_10") (pintype "passive"))
    )
    (net (code "124") (name "Net-(U11-~{Y}6)") (class "Default")
      (node (ref "LED4") (pin "2") (pinfunction "2_2") (pintype "passive"))
      (node (ref "U11") (pin "9") (pinfunction "~{Y}6_9") (pintype "passive"))
    )
    (net (code "125") (name "Net-(U11-~{Y}7)") (class "Default")
      (node (ref "LED3") (pin "2") (pinfunction "2_2") (pintype "passive"))
      (node (ref "U11") (pin "7") (pinfunction "~{Y}7_7") (pintype "passive"))
    )
    (net (code "126") (name "V-") (class "Default")
      (node (ref "P1") (pin "19") (pinfunction "19_19") (pintype "passive"))
      (node (ref "P1") (pin "20") (pinfunction "20_20") (pintype "passive"))
      (node (ref "P2") (pin "19") (pinfunction "19_19") (pintype "passive"))
      (node (ref "P2") (pin "20") (pinfunction "20_20") (pintype "passive"))
      (node (ref "U6") (pin "1") (pinfunction "V-_1") (pintype "passive"))
    )
    (net (code "127") (name "VCC") (class "Default")
      (node (ref "BUZZER1") (pin "1") (pinfunction "+_1") (pintype "passive"))
      (node (ref "C10") (pin "1") (pinfunction "1_1") (pintype "passive"))
      (node (ref "C11") (pin "1") (pinfunction "1_1") (pintype "passive"))
      (node (ref "C14") (pin "2") (pinfunction "2_2") (pintype "passive"))
      (node (ref "C16") (pin "1") (pinfunction "1_1") (pintype "passive"))
      (node (ref "C17") (pin "1") (pinfunction "1_1") (pintype "passive"))
      (node (ref "C7") (pin "1") (pinfunction "1_1") (pintype "passive"))
      (node (ref "C8") (pin "1") (pinfunction "1_1") (pintype "passive"))
      (node (ref "C9") (pin "1") (pinfunction "1_1") (pintype "passive"))
      (node (ref "MOS1") (pin "3") (pinfunction "D_3") (pintype "passive"))
      (node (ref "OLED1") (pin "2") (pinfunction "VCC_2") (pintype "passive"))
      (node (ref "P11") (pin "1") (pinfunction "1_1") (pintype "passive"))
      (node (ref "P11") (pin "2") (pinfunction "2_2") (pintype "passive"))
      (node (ref "P11") (pin "3") (pinfunction "3_3") (pintype "passive"))
      (node (ref "P11") (pin "4") (pinfunction "4_4") (pintype "passive"))
      (node (ref "P4") (pin "17") (pinfunction "17_17") (pintype "passive"))
      (node (ref "P4") (pin "18") (pinfunction "18_18") (pintype "passive"))
      (node (ref "R10") (pin "2") (pintype "passive"))
      (node (ref "R11") (pin "2") (pintype "passive"))
      (node (ref "R12") (pin "2") (pintype "passive"))
      (node (ref "R13") (pin "2") (pintype "passive"))
      (node (ref "R14") (pin "1") (pintype "passive"))
      (node (ref "R15") (pin "1") (pintype "passive"))
      (node (ref "R16") (pin "1") (pintype "passive"))
      (node (ref "R17") (pin "1") (pintype "passive"))
      (node (ref "R18") (pin "1") (pintype "passive"))
      (node (ref "R19") (pin "1") (pintype "passive"))
      (node (ref "R20") (pin "1") (pintype "passive"))
      (node (ref "R21") (pin "1") (pintype "passive"))
      (node (ref "R3") (pin "2") (pintype "passive"))
      (node (ref "R4") (pin "2") (pintype "passive"))
      (node (ref "R5") (pin "1") (pintype "passive"))
      (node (ref "R6") (pin "1") (pintype "passive"))
      (node (ref "R9") (pin "2") (pintype "passive"))
      (node (ref "U10") (pin "1") (pinfunction "VDD_1") (pintype "passive"))
      (node (ref "U11") (pin "16") (pinfunction "VCC_16") (pintype "passive"))
      (node (ref "U12") (pin "1") (pinfunction "A0_1") (pintype "passive"))
      (node (ref "U12") (pin "2") (pinfunction "A1_2") (pintype "passive"))
      (node (ref "U12") (pin "3") (pinfunction "A2_3") (pintype "passive"))
      (node (ref "U12") (pin "8") (pinfunction "VCC_8") (pintype "passive"))
      (node (ref "U13") (pin "2") (pinfunction "VCC_2") (pintype "passive"))
      (node (ref "U2") (pin "3") (pinfunction "VIN_3") (pintype "passive"))
      (node (ref "U3") (pin "10") (pinfunction "*SRCLR_10") (pintype "passive"))
      (node (ref "U3") (pin "16") (pinfunction "VCC_16") (pintype "passive"))
      (node (ref "U4") (pin "10") (pinfunction "*SRCLR_10") (pintype "passive"))
      (node (ref "U4") (pin "16") (pinfunction "VCC_16") (pintype "passive"))
      (node (ref "U5") (pin "8") (pinfunction "VCC_8") (pintype "passive"))
      (node (ref "U7") (pin "1") (pinfunction "VCC_1") (pintype "passive"))
      (node (ref "U8") (pin "9") (pinfunction "COM_9") (pintype "passive"))
      (node (ref "U9") (pin "2") (pinfunction "VCC_2") (pintype "passive"))
    )
    (net (code "128") (name "VIN") (class "Default")
      (node (ref "P3") (pin "19") (pinfunction "19_19") (pintype "passive"))
      (node (ref "P3") (pin "20") (pinfunction "20_20") (pintype "passive"))
      (node (ref "P4") (pin "19") (pinfunction "19_19") (pintype "passive"))
      (node (ref "P4") (pin "20") (pinfunction "20_20") (pintype "passive"))
      (node (ref "U6") (pin "44") (pinfunction "VIN_44") (pintype "passive"))
    )
    (net (code "129") (name "unconnected-(P1-Pad7)") (class "Default")
      (node (ref "P1") (pin "7") (pinfunction "7_7") (pintype "passive"))
    )
    (net (code "130") (name "unconnected-(P1-Pad8)") (class "Default")
      (node (ref "P1") (pin "8") (pinfunction "8_8") (pintype "passive"))
    )
    (net (code "131") (name "unconnected-(U3-QH'-Pad9)") (class "Default")
      (node (ref "U3") (pin "9") (pinfunction "QH'_9") (pintype "passive+no_connect"))
    )
    (net (code "132") (name "unconnected-(U4-QE-Pad4)") (class "Default")
      (node (ref "U4") (pin "4") (pinfunction "QE_4") (pintype "passive+no_connect"))
    )
    (net (code "133") (name "unconnected-(U4-QF-Pad5)") (class "Default")
      (node (ref "U4") (pin "5") (pinfunction "QF_5") (pintype "passive+no_connect"))
    )
    (net (code "134") (name "unconnected-(U4-QG-Pad6)") (class "Default")
      (node (ref "U4") (pin "6") (pinfunction "QG_6") (pintype "passive+no_connect"))
    )
    (net (code "135") (name "unconnected-(U4-QH-Pad7)") (class "Default")
      (node (ref "U4") (pin "7") (pinfunction "QH_7") (pintype "passive+no_connect"))
    )
    (net (code "136") (name "unconnected-(U8-IN6-Pad6)") (class "Default")
      (node (ref "U8") (pin "6") (pinfunction "IN6_6") (pintype "passive"))
    )
    (net (code "137") (name "unconnected-(U8-IN7-Pad7)") (class "Default")
      (node (ref "U8") (pin "7") (pinfunction "IN7_7") (pintype "passive"))
    )
    (net (code "138") (name "unconnected-(U8-OUT6-Pad11)") (class "Default")
      (node (ref "U8") (pin "11") (pinfunction "OUT6_11") (pintype "passive"))
    )
    (net (code "139") (name "unconnected-(U8-OUT7-Pad10)") (class "Default")
      (node (ref "U8") (pin "10") (pinfunction "OUT7_10") (pintype "passive"))
    )
    (net (code "140") (name "unconnected-(U10-NC-Pad3)") (class "Default")
      (node (ref "U10") (pin "3") (pinfunction "NC_3") (pintype "passive"))
    )
    (net (code "141") (name "unconnected-(U11-E3-Pad6)") (class "Default")
      (node (ref "U11") (pin "6") (pinfunction "E3_6") (pintype "passive"))
    )
    (net (code "142") (name "unconnected-(U13-32KHz-Pad1)") (class "Default")
      (node (ref "U13") (pin "1") (pinfunction "32KHz_1") (pintype "passive"))
    )
    (net (code "143") (name "unconnected-(U13-~{INT}{slash}SQW-Pad3)") (class "Default")
      (node (ref "U13") (pin "3") (pinfunction "~{INT}/SQW_3") (pintype "passive+no_connect"))
    )
    (net (code "144") (name "unconnected-(U13-~{RST}-Pad4)") (class "Default")
      (node (ref "U13") (pin "4") (pinfunction "~{RST}_4") (pintype "passive+no_connect"))
    )
    (net (code "145") (name "unconnected-(xh1-Pad5)") (class "Default")
      (node (ref "xh1") (pin "5") (pinfunction "5_5") (pintype "passive"))
    )
  )
)
